# Haptic_Schematic.net
KiCad netlist of a schematic drawn in EAGLE
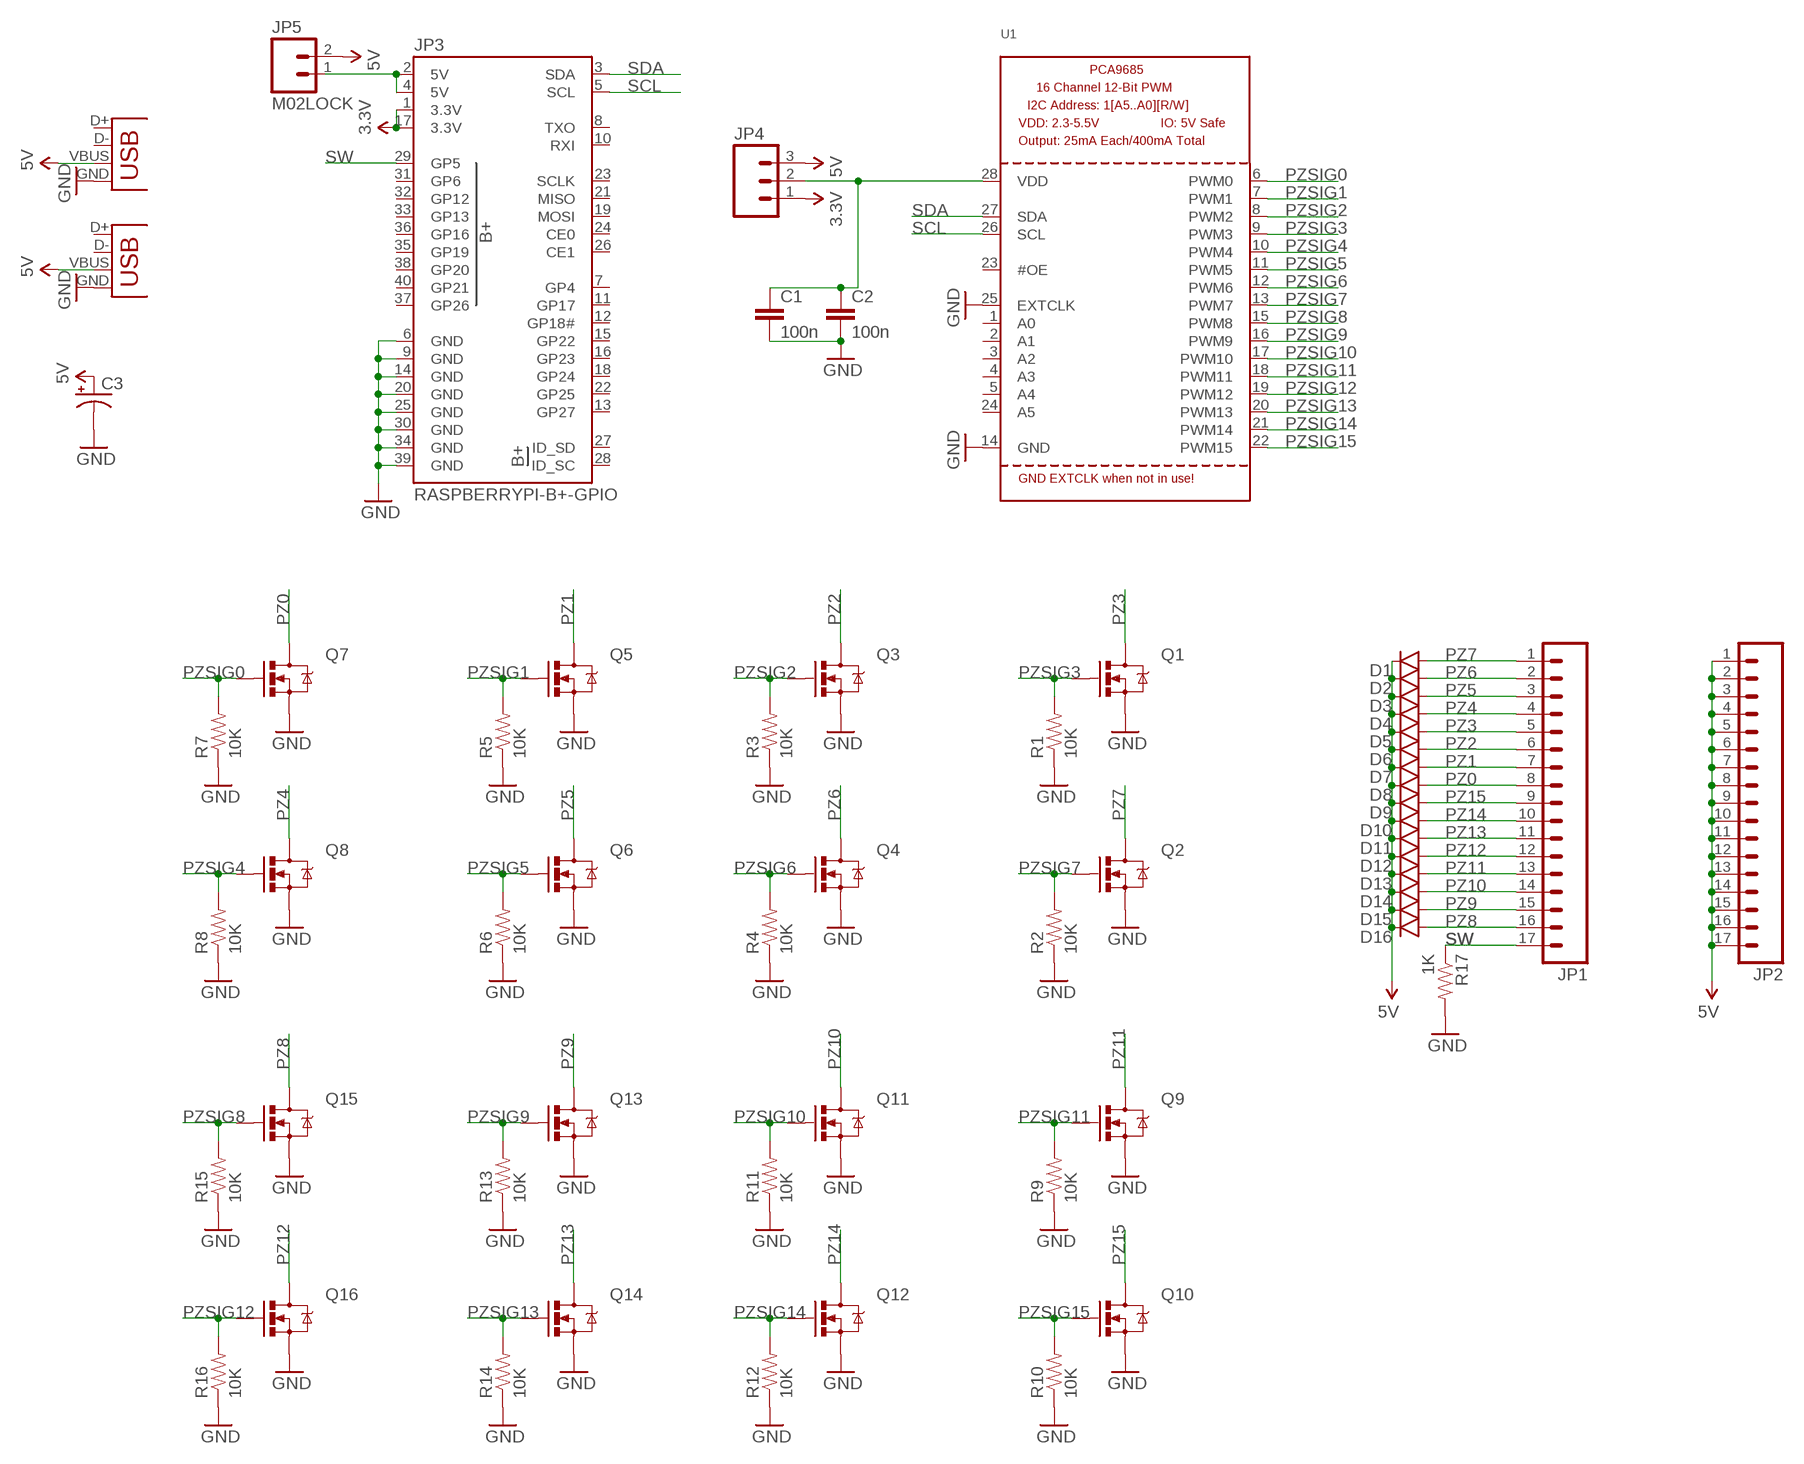
[diagram p0: schematic, sheet 1]

(export (version "E")
  (design (tool "Eeschema 10.0.6"))
  (components
    (comp (ref "C1")
      (value "100n")
      (footprint "eagle-import:0805")
      (libsource (lib "eagle-import") (part "CAP0805"))
    )
    (comp (ref "C2")
      (value "100n")
      (footprint "eagle-import:0805")
      (libsource (lib "eagle-import") (part "CAP0805"))
    )
    (comp (ref "C3")
      (value "CAP_POLPTH2")
      (footprint "eagle-import:CPOL-RADIAL-10UF-25V")
      (libsource (lib "eagle-import") (part "CAP_POLPTH2"))
    )
    (comp (ref "D1")
      (value "DIODESOD523")
      (footprint "eagle-import:SOD523")
      (libsource (lib "eagle-import") (part "DIODESOD523"))
    )
    (comp (ref "D2")
      (value "DIODESOD523")
      (footprint "eagle-import:SOD523")
      (libsource (lib "eagle-import") (part "DIODESOD523"))
    )
    (comp (ref "D3")
      (value "DIODESOD523")
      (footprint "eagle-import:SOD523")
      (libsource (lib "eagle-import") (part "DIODESOD523"))
    )
    (comp (ref "D4")
      (value "DIODESOD523")
      (footprint "eagle-import:SOD523")
      (libsource (lib "eagle-import") (part "DIODESOD523"))
    )
    (comp (ref "D5")
      (value "DIODESOD523")
      (footprint "eagle-import:SOD523")
      (libsource (lib "eagle-import") (part "DIODESOD523"))
    )
    (comp (ref "D6")
      (value "DIODESOD523")
      (footprint "eagle-import:SOD523")
      (libsource (lib "eagle-import") (part "DIODESOD523"))
    )
    (comp (ref "D7")
      (value "DIODESOD523")
      (footprint "eagle-import:SOD523")
      (libsource (lib "eagle-import") (part "DIODESOD523"))
    )
    (comp (ref "D8")
      (value "DIODESOD523")
      (footprint "eagle-import:SOD523")
      (libsource (lib "eagle-import") (part "DIODESOD523"))
    )
    (comp (ref "D9")
      (value "DIODESOD523")
      (footprint "eagle-import:SOD523")
      (libsource (lib "eagle-import") (part "DIODESOD523"))
    )
    (comp (ref "D10")
      (value "DIODESOD523")
      (footprint "eagle-import:SOD523")
      (libsource (lib "eagle-import") (part "DIODESOD523"))
    )
    (comp (ref "D11")
      (value "DIODESOD523")
      (footprint "eagle-import:SOD523")
      (libsource (lib "eagle-import") (part "DIODESOD523"))
    )
    (comp (ref "D12")
      (value "DIODESOD523")
      (footprint "eagle-import:SOD523")
      (libsource (lib "eagle-import") (part "DIODESOD523"))
    )
    (comp (ref "D13")
      (value "DIODESOD523")
      (footprint "eagle-import:SOD523")
      (libsource (lib "eagle-import") (part "DIODESOD523"))
    )
    (comp (ref "D14")
      (value "DIODESOD523")
      (footprint "eagle-import:SOD523")
      (libsource (lib "eagle-import") (part "DIODESOD523"))
    )
    (comp (ref "D15")
      (value "DIODESOD523")
      (footprint "eagle-import:SOD523")
      (libsource (lib "eagle-import") (part "DIODESOD523"))
    )
    (comp (ref "D16")
      (value "DIODESOD523")
      (footprint "eagle-import:SOD523")
      (libsource (lib "eagle-import") (part "DIODESOD523"))
    )
    (comp (ref "JP1")
      (value "M17")
      (footprint "eagle-import:1X17")
      (libsource (lib "eagle-import") (part "M17"))
    )
    (comp (ref "JP2")
      (value "M17")
      (footprint "eagle-import:1X17")
      (libsource (lib "eagle-import") (part "M17"))
    )
    (comp (ref "JP3")
      (value "RASPBERRYPI-B+-GPIO")
      (footprint "eagle-import:2X20-SHROUDED")
      (libsource (lib "eagle-import") (part "RASPBERRYPI-B+-GPIO"))
    )
    (comp (ref "JP4")
      (value "M03LOCK")
      (footprint "eagle-import:1X03_LOCK")
      (libsource (lib "eagle-import") (part "M03LOCK"))
    )
    (comp (ref "JP5")
      (value "M02LOCK")
      (footprint "eagle-import:1X02_LOCK")
      (libsource (lib "eagle-import") (part "M02LOCK"))
    )
    (comp (ref "JP6")
      (value "USB-B")
      (footprint "eagle-import:USB-B-PTH")
      (libsource (lib "eagle-import") (part "USBPTH"))
    )
    (comp (ref "JP7")
      (value "USB-B")
      (footprint "eagle-import:USB-B-PTH")
      (libsource (lib "eagle-import") (part "USBPTH"))
    )
    (comp (ref "Q1")
      (value "MOSFET-NCHANNEL2N7002PW")
      (footprint "eagle-import:SOT323")
      (libsource (lib "eagle-import") (part "MOSFET-NCHANNEL2N7002PW"))
    )
    (comp (ref "Q2")
      (value "MOSFET-NCHANNEL2N7002PW")
      (footprint "eagle-import:SOT323")
      (libsource (lib "eagle-import") (part "MOSFET-NCHANNEL2N7002PW"))
    )
    (comp (ref "Q3")
      (value "MOSFET-NCHANNEL2N7002PW")
      (footprint "eagle-import:SOT323")
      (libsource (lib "eagle-import") (part "MOSFET-NCHANNEL2N7002PW"))
    )
    (comp (ref "Q4")
      (value "MOSFET-NCHANNEL2N7002PW")
      (footprint "eagle-import:SOT323")
      (libsource (lib "eagle-import") (part "MOSFET-NCHANNEL2N7002PW"))
    )
    (comp (ref "Q5")
      (value "MOSFET-NCHANNEL2N7002PW")
      (footprint "eagle-import:SOT323")
      (libsource (lib "eagle-import") (part "MOSFET-NCHANNEL2N7002PW"))
    )
    (comp (ref "Q6")
      (value "MOSFET-NCHANNEL2N7002PW")
      (footprint "eagle-import:SOT323")
      (libsource (lib "eagle-import") (part "MOSFET-NCHANNEL2N7002PW"))
    )
    (comp (ref "Q7")
      (value "MOSFET-NCHANNEL2N7002PW")
      (footprint "eagle-import:SOT323")
      (libsource (lib "eagle-import") (part "MOSFET-NCHANNEL2N7002PW"))
    )
    (comp (ref "Q8")
      (value "MOSFET-NCHANNEL2N7002PW")
      (footprint "eagle-import:SOT323")
      (libsource (lib "eagle-import") (part "MOSFET-NCHANNEL2N7002PW"))
    )
    (comp (ref "Q9")
      (value "MOSFET-NCHANNEL2N7002PW")
      (footprint "eagle-import:SOT323")
      (libsource (lib "eagle-import") (part "MOSFET-NCHANNEL2N7002PW"))
    )
    (comp (ref "Q10")
      (value "MOSFET-NCHANNEL2N7002PW")
      (footprint "eagle-import:SOT323")
      (libsource (lib "eagle-import") (part "MOSFET-NCHANNEL2N7002PW"))
    )
    (comp (ref "Q11")
      (value "MOSFET-NCHANNEL2N7002PW")
      (footprint "eagle-import:SOT323")
      (libsource (lib "eagle-import") (part "MOSFET-NCHANNEL2N7002PW"))
    )
    (comp (ref "Q12")
      (value "MOSFET-NCHANNEL2N7002PW")
      (footprint "eagle-import:SOT323")
      (libsource (lib "eagle-import") (part "MOSFET-NCHANNEL2N7002PW"))
    )
    (comp (ref "Q13")
      (value "MOSFET-NCHANNEL2N7002PW")
      (footprint "eagle-import:SOT323")
      (libsource (lib "eagle-import") (part "MOSFET-NCHANNEL2N7002PW"))
    )
    (comp (ref "Q14")
      (value "MOSFET-NCHANNEL2N7002PW")
      (footprint "eagle-import:SOT323")
      (libsource (lib "eagle-import") (part "MOSFET-NCHANNEL2N7002PW"))
    )
    (comp (ref "Q15")
      (value "MOSFET-NCHANNEL2N7002PW")
      (footprint "eagle-import:SOT323")
      (libsource (lib "eagle-import") (part "MOSFET-NCHANNEL2N7002PW"))
    )
    (comp (ref "Q16")
      (value "MOSFET-NCHANNEL2N7002PW")
      (footprint "eagle-import:SOT323")
      (libsource (lib "eagle-import") (part "MOSFET-NCHANNEL2N7002PW"))
    )
    (comp (ref "R1")
      (value "10K")
      (footprint "eagle-import:0805")
      (libsource (lib "eagle-import") (part "RESISTOR0805-RES"))
    )
    (comp (ref "R2")
      (value "10K")
      (footprint "eagle-import:0805")
      (libsource (lib "eagle-import") (part "RESISTOR0805-RES"))
    )
    (comp (ref "R3")
      (value "10K")
      (footprint "eagle-import:0805")
      (libsource (lib "eagle-import") (part "RESISTOR0805-RES"))
    )
    (comp (ref "R4")
      (value "10K")
      (footprint "eagle-import:0805")
      (libsource (lib "eagle-import") (part "RESISTOR0805-RES"))
    )
    (comp (ref "R5")
      (value "10K")
      (footprint "eagle-import:0805")
      (libsource (lib "eagle-import") (part "RESISTOR0805-RES"))
    )
    (comp (ref "R6")
      (value "10K")
      (footprint "eagle-import:0805")
      (libsource (lib "eagle-import") (part "RESISTOR0805-RES"))
    )
    (comp (ref "R7")
      (value "10K")
      (footprint "eagle-import:0805")
      (libsource (lib "eagle-import") (part "RESISTOR0805-RES"))
    )
    (comp (ref "R8")
      (value "10K")
      (footprint "eagle-import:0805")
      (libsource (lib "eagle-import") (part "RESISTOR0805-RES"))
    )
    (comp (ref "R9")
      (value "10K")
      (footprint "eagle-import:0805")
      (libsource (lib "eagle-import") (part "RESISTOR0805-RES"))
    )
    (comp (ref "R10")
      (value "10K")
      (footprint "eagle-import:0805")
      (libsource (lib "eagle-import") (part "RESISTOR0805-RES"))
    )
    (comp (ref "R11")
      (value "10K")
      (footprint "eagle-import:0805")
      (libsource (lib "eagle-import") (part "RESISTOR0805-RES"))
    )
    (comp (ref "R12")
      (value "10K")
      (footprint "eagle-import:0805")
      (libsource (lib "eagle-import") (part "RESISTOR0805-RES"))
    )
    (comp (ref "R13")
      (value "10K")
      (footprint "eagle-import:0805")
      (libsource (lib "eagle-import") (part "RESISTOR0805-RES"))
    )
    (comp (ref "R14")
      (value "10K")
      (footprint "eagle-import:0805")
      (libsource (lib "eagle-import") (part "RESISTOR0805-RES"))
    )
    (comp (ref "R15")
      (value "10K")
      (footprint "eagle-import:0805")
      (libsource (lib "eagle-import") (part "RESISTOR0805-RES"))
    )
    (comp (ref "R16")
      (value "10K")
      (footprint "eagle-import:0805")
      (libsource (lib "eagle-import") (part "RESISTOR0805-RES"))
    )
    (comp (ref "R17")
      (value "1K")
      (footprint "eagle-import:0805")
      (libsource (lib "eagle-import") (part "RESISTOR0805-RES"))
    )
    (comp (ref "U1")
      (value "PCA9685")
      (footprint "eagle-import:TSSOP28")
      (libsource (lib "eagle-import") (part "PCA9685"))
    )
  )
  (nets
    (net (code "1") (name "/PZ0") (class "Default")
      (node (ref "D8") (pin "A") (pinfunction "A_A") (pintype "passive"))
      (node (ref "JP1") (pin "8") (pinfunction "8_8") (pintype "passive"))
      (node (ref "Q7") (pin "3") (pinfunction "D_3") (pintype "passive"))
    )
    (net (code "2") (name "/PZ1") (class "Default")
      (node (ref "D7") (pin "A") (pinfunction "A_A") (pintype "passive"))
      (node (ref "JP1") (pin "7") (pinfunction "7_7") (pintype "passive"))
      (node (ref "Q5") (pin "3") (pinfunction "D_3") (pintype "passive"))
    )
    (net (code "3") (name "/PZ2") (class "Default")
      (node (ref "D6") (pin "A") (pinfunction "A_A") (pintype "passive"))
      (node (ref "JP1") (pin "6") (pinfunction "6_6") (pintype "passive"))
      (node (ref "Q3") (pin "3") (pinfunction "D_3") (pintype "passive"))
    )
    (net (code "4") (name "/PZ3") (class "Default")
      (node (ref "D5") (pin "A") (pinfunction "A_A") (pintype "passive"))
      (node (ref "JP1") (pin "5") (pinfunction "5_5") (pintype "passive"))
      (node (ref "Q1") (pin "3") (pinfunction "D_3") (pintype "passive"))
    )
    (net (code "5") (name "/PZ4") (class "Default")
      (node (ref "D4") (pin "A") (pinfunction "A_A") (pintype "passive"))
      (node (ref "JP1") (pin "4") (pinfunction "4_4") (pintype "passive"))
      (node (ref "Q8") (pin "3") (pinfunction "D_3") (pintype "passive"))
    )
    (net (code "6") (name "/PZ5") (class "Default")
      (node (ref "D3") (pin "A") (pinfunction "A_A") (pintype "passive"))
      (node (ref "JP1") (pin "3") (pinfunction "3_3") (pintype "passive"))
      (node (ref "Q6") (pin "3") (pinfunction "D_3") (pintype "passive"))
    )
    (net (code "7") (name "/PZ6") (class "Default")
      (node (ref "D2") (pin "A") (pinfunction "A_A") (pintype "passive"))
      (node (ref "JP1") (pin "2") (pinfunction "2_2") (pintype "passive"))
      (node (ref "Q4") (pin "3") (pinfunction "D_3") (pintype "passive"))
    )
    (net (code "8") (name "/PZ7") (class "Default")
      (node (ref "D1") (pin "A") (pinfunction "A_A") (pintype "passive"))
      (node (ref "JP1") (pin "1") (pinfunction "1_1") (pintype "passive"))
      (node (ref "Q2") (pin "3") (pinfunction "D_3") (pintype "passive"))
    )
    (net (code "9") (name "/PZ8") (class "Default")
      (node (ref "D16") (pin "A") (pinfunction "A_A") (pintype "passive"))
      (node (ref "JP1") (pin "16") (pinfunction "16_16") (pintype "passive"))
      (node (ref "Q15") (pin "3") (pinfunction "D_3") (pintype "passive"))
    )
    (net (code "10") (name "/PZ9") (class "Default")
      (node (ref "D15") (pin "A") (pinfunction "A_A") (pintype "passive"))
      (node (ref "JP1") (pin "15") (pinfunction "15_15") (pintype "passive"))
      (node (ref "Q13") (pin "3") (pinfunction "D_3") (pintype "passive"))
    )
    (net (code "11") (name "/PZ10") (class "Default")
      (node (ref "D14") (pin "A") (pinfunction "A_A") (pintype "passive"))
      (node (ref "JP1") (pin "14") (pinfunction "14_14") (pintype "passive"))
      (node (ref "Q11") (pin "3") (pinfunction "D_3") (pintype "passive"))
    )
    (net (code "12") (name "/PZ11") (class "Default")
      (node (ref "D13") (pin "A") (pinfunction "A_A") (pintype "passive"))
      (node (ref "JP1") (pin "13") (pinfunction "13_13") (pintype "passive"))
      (node (ref "Q9") (pin "3") (pinfunction "D_3") (pintype "passive"))
    )
    (net (code "13") (name "/PZ12") (class "Default")
      (node (ref "D12") (pin "A") (pinfunction "A_A") (pintype "passive"))
      (node (ref "JP1") (pin "12") (pinfunction "12_12") (pintype "passive"))
      (node (ref "Q16") (pin "3") (pinfunction "D_3") (pintype "passive"))
    )
    (net (code "14") (name "/PZ13") (class "Default")
      (node (ref "D11") (pin "A") (pinfunction "A_A") (pintype "passive"))
      (node (ref "JP1") (pin "11") (pinfunction "11_11") (pintype "passive"))
      (node (ref "Q14") (pin "3") (pinfunction "D_3") (pintype "passive"))
    )
    (net (code "15") (name "/PZ14") (class "Default")
      (node (ref "D10") (pin "A") (pinfunction "A_A") (pintype "passive"))
      (node (ref "JP1") (pin "10") (pinfunction "10_10") (pintype "passive"))
      (node (ref "Q12") (pin "3") (pinfunction "D_3") (pintype "passive"))
    )
    (net (code "16") (name "/PZ15") (class "Default")
      (node (ref "D9") (pin "A") (pinfunction "A_A") (pintype "passive"))
      (node (ref "JP1") (pin "9") (pinfunction "9_9") (pintype "passive"))
      (node (ref "Q10") (pin "3") (pinfunction "D_3") (pintype "passive"))
    )
    (net (code "17") (name "/PZSIG0") (class "Default")
      (node (ref "Q7") (pin "1") (pinfunction "G_1") (pintype "passive"))
      (node (ref "R7") (pin "2") (pinfunction "2_2") (pintype "passive"))
      (node (ref "U1") (pin "6") (pinfunction "PWM0_6") (pintype "output"))
    )
    (net (code "18") (name "/PZSIG1") (class "Default")
      (node (ref "Q5") (pin "1") (pinfunction "G_1") (pintype "passive"))
      (node (ref "R5") (pin "2") (pinfunction "2_2") (pintype "passive"))
      (node (ref "U1") (pin "7") (pinfunction "PWM1_7") (pintype "output"))
    )
    (net (code "19") (name "/PZSIG2") (class "Default")
      (node (ref "Q3") (pin "1") (pinfunction "G_1") (pintype "passive"))
      (node (ref "R3") (pin "2") (pinfunction "2_2") (pintype "passive"))
      (node (ref "U1") (pin "8") (pinfunction "PWM2_8") (pintype "output"))
    )
    (net (code "20") (name "/PZSIG3") (class "Default")
      (node (ref "Q1") (pin "1") (pinfunction "G_1") (pintype "passive"))
      (node (ref "R1") (pin "2") (pinfunction "2_2") (pintype "passive"))
      (node (ref "U1") (pin "9") (pinfunction "PWM3_9") (pintype "output"))
    )
    (net (code "21") (name "/PZSIG4") (class "Default")
      (node (ref "Q8") (pin "1") (pinfunction "G_1") (pintype "passive"))
      (node (ref "R8") (pin "2") (pinfunction "2_2") (pintype "passive"))
      (node (ref "U1") (pin "10") (pinfunction "PWM4_10") (pintype "output"))
    )
    (net (code "22") (name "/PZSIG5") (class "Default")
      (node (ref "Q6") (pin "1") (pinfunction "G_1") (pintype "passive"))
      (node (ref "R6") (pin "2") (pinfunction "2_2") (pintype "passive"))
      (node (ref "U1") (pin "11") (pinfunction "PWM5_11") (pintype "output"))
    )
    (net (code "23") (name "/PZSIG6") (class "Default")
      (node (ref "Q4") (pin "1") (pinfunction "G_1") (pintype "passive"))
      (node (ref "R4") (pin "2") (pinfunction "2_2") (pintype "passive"))
      (node (ref "U1") (pin "12") (pinfunction "PWM6_12") (pintype "output"))
    )
    (net (code "24") (name "/PZSIG7") (class "Default")
      (node (ref "Q2") (pin "1") (pinfunction "G_1") (pintype "passive"))
      (node (ref "R2") (pin "2") (pinfunction "2_2") (pintype "passive"))
      (node (ref "U1") (pin "13") (pinfunction "PWM7_13") (pintype "output"))
    )
    (net (code "25") (name "/PZSIG8") (class "Default")
      (node (ref "Q15") (pin "1") (pinfunction "G_1") (pintype "passive"))
      (node (ref "R15") (pin "2") (pinfunction "2_2") (pintype "passive"))
      (node (ref "U1") (pin "15") (pinfunction "PWM8_15") (pintype "output"))
    )
    (net (code "26") (name "/PZSIG9") (class "Default")
      (node (ref "Q13") (pin "1") (pinfunction "G_1") (pintype "passive"))
      (node (ref "R13") (pin "2") (pinfunction "2_2") (pintype "passive"))
      (node (ref "U1") (pin "16") (pinfunction "PWM9_16") (pintype "output"))
    )
    (net (code "27") (name "/PZSIG10") (class "Default")
      (node (ref "Q11") (pin "1") (pinfunction "G_1") (pintype "passive"))
      (node (ref "R11") (pin "2") (pinfunction "2_2") (pintype "passive"))
      (node (ref "U1") (pin "17") (pinfunction "PWM10_17") (pintype "output"))
    )
    (net (code "28") (name "/PZSIG11") (class "Default")
      (node (ref "Q9") (pin "1") (pinfunction "G_1") (pintype "passive"))
      (node (ref "R9") (pin "2") (pinfunction "2_2") (pintype "passive"))
      (node (ref "U1") (pin "18") (pinfunction "PWM11_18") (pintype "output"))
    )
    (net (code "29") (name "/PZSIG12") (class "Default")
      (node (ref "Q16") (pin "1") (pinfunction "G_1") (pintype "passive"))
      (node (ref "R16") (pin "2") (pinfunction "2_2") (pintype "passive"))
      (node (ref "U1") (pin "19") (pinfunction "PWM12_19") (pintype "output"))
    )
    (net (code "30") (name "/PZSIG13") (class "Default")
      (node (ref "Q14") (pin "1") (pinfunction "G_1") (pintype "passive"))
      (node (ref "R14") (pin "2") (pinfunction "2_2") (pintype "passive"))
      (node (ref "U1") (pin "20") (pinfunction "PWM13_20") (pintype "output"))
    )
    (net (code "31") (name "/PZSIG14") (class "Default")
      (node (ref "Q12") (pin "1") (pinfunction "G_1") (pintype "passive"))
      (node (ref "R12") (pin "2") (pinfunction "2_2") (pintype "passive"))
      (node (ref "U1") (pin "21") (pinfunction "PWM14_21") (pintype "output"))
    )
    (net (code "32") (name "/PZSIG15") (class "Default")
      (node (ref "Q10") (pin "1") (pinfunction "G_1") (pintype "passive"))
      (node (ref "R10") (pin "2") (pinfunction "2_2") (pintype "passive"))
      (node (ref "U1") (pin "22") (pinfunction "PWM15_22") (pintype "output"))
    )
    (net (code "33") (name "/SCL") (class "Default")
      (node (ref "JP3") (pin "5") (pinfunction "SCL_5") (pintype "bidirectional"))
      (node (ref "U1") (pin "26") (pinfunction "SCL_26") (pintype "bidirectional"))
    )
    (net (code "34") (name "/SDA") (class "Default")
      (node (ref "JP3") (pin "3") (pinfunction "SDA_3") (pintype "bidirectional"))
      (node (ref "U1") (pin "27") (pinfunction "SDA_27") (pintype "bidirectional"))
    )
    (net (code "35") (name "/SW") (class "Default")
      (node (ref "JP1") (pin "17") (pinfunction "17_17") (pintype "passive"))
      (node (ref "JP3") (pin "29") (pinfunction "GP5_29") (pintype "bidirectional"))
      (node (ref "R17") (pin "1") (pinfunction "1_1") (pintype "passive"))
    )
    (net (code "36") (name "3.3V") (class "Default")
      (node (ref "JP3") (pin "1") (pinfunction "3.3V_1") (pintype "power_in"))
      (node (ref "JP3") (pin "17") (pinfunction "3.3V_17") (pintype "power_in"))
      (node (ref "JP4") (pin "1") (pinfunction "1_1") (pintype "passive"))
    )
    (net (code "37") (name "5V") (class "Default")
      (node (ref "C3") (pin "1") (pinfunction "+_1") (pintype "passive"))
      (node (ref "D1") (pin "C") (pinfunction "C_C") (pintype "passive"))
      (node (ref "D10") (pin "C") (pinfunction "C_C") (pintype "passive"))
      (node (ref "D11") (pin "C") (pinfunction "C_C") (pintype "passive"))
      (node (ref "D12") (pin "C") (pinfunction "C_C") (pintype "passive"))
      (node (ref "D13") (pin "C") (pinfunction "C_C") (pintype "passive"))
      (node (ref "D14") (pin "C") (pinfunction "C_C") (pintype "passive"))
      (node (ref "D15") (pin "C") (pinfunction "C_C") (pintype "passive"))
      (node (ref "D16") (pin "C") (pinfunction "C_C") (pintype "passive"))
      (node (ref "D2") (pin "C") (pinfunction "C_C") (pintype "passive"))
      (node (ref "D3") (pin "C") (pinfunction "C_C") (pintype "passive"))
      (node (ref "D4") (pin "C") (pinfunction "C_C") (pintype "passive"))
      (node (ref "D5") (pin "C") (pinfunction "C_C") (pintype "passive"))
      (node (ref "D6") (pin "C") (pinfunction "C_C") (pintype "passive"))
      (node (ref "D7") (pin "C") (pinfunction "C_C") (pintype "passive"))
      (node (ref "D8") (pin "C") (pinfunction "C_C") (pintype "passive"))
      (node (ref "D9") (pin "C") (pinfunction "C_C") (pintype "passive"))
      (node (ref "JP2") (pin "1") (pinfunction "1_1") (pintype "passive"))
      (node (ref "JP2") (pin "10") (pinfunction "10_10") (pintype "passive"))
      (node (ref "JP2") (pin "11") (pinfunction "11_11") (pintype "passive"))
      (node (ref "JP2") (pin "12") (pinfunction "12_12") (pintype "passive"))
      (node (ref "JP2") (pin "13") (pinfunction "13_13") (pintype "passive"))
      (node (ref "JP2") (pin "14") (pinfunction "14_14") (pintype "passive"))
      (node (ref "JP2") (pin "15") (pinfunction "15_15") (pintype "passive"))
      (node (ref "JP2") (pin "16") (pinfunction "16_16") (pintype "passive"))
      (node (ref "JP2") (pin "17") (pinfunction "17_17") (pintype "passive"))
      (node (ref "JP2") (pin "2") (pinfunction "2_2") (pintype "passive"))
      (node (ref "JP2") (pin "3") (pinfunction "3_3") (pintype "passive"))
      (node (ref "JP2") (pin "4") (pinfunction "4_4") (pintype "passive"))
      (node (ref "JP2") (pin "5") (pinfunction "5_5") (pintype "passive"))
      (node (ref "JP2") (pin "6") (pinfunction "6_6") (pintype "passive"))
      (node (ref "JP2") (pin "7") (pinfunction "7_7") (pintype "passive"))
      (node (ref "JP2") (pin "8") (pinfunction "8_8") (pintype "passive"))
      (node (ref "JP2") (pin "9") (pinfunction "9_9") (pintype "passive"))
      (node (ref "JP4") (pin "3") (pinfunction "3_3") (pintype "passive"))
      (node (ref "JP5") (pin "2") (pinfunction "2_2") (pintype "passive"))
      (node (ref "JP6") (pin "VBUS") (pinfunction "VBUS_VBUS") (pintype "bidirectional"))
      (node (ref "JP7") (pin "VBUS") (pinfunction "VBUS_VBUS") (pintype "bidirectional"))
    )
    (net (code "38") (name "GND") (class "Default")
      (node (ref "C1") (pin "2") (pinfunction "2_2") (pintype "passive"))
      (node (ref "C2") (pin "2") (pinfunction "2_2") (pintype "passive"))
      (node (ref "C3") (pin "2") (pinfunction "-_2") (pintype "passive"))
      (node (ref "JP3") (pin "14") (pinfunction "GND_14") (pintype "power_in"))
      (node (ref "JP3") (pin "20") (pinfunction "GND_20") (pintype "power_in"))
      (node (ref "JP3") (pin "25") (pinfunction "GND_25") (pintype "power_in"))
      (node (ref "JP3") (pin "30") (pinfunction "GND_30") (pintype "power_in"))
      (node (ref "JP3") (pin "34") (pinfunction "GND_34") (pintype "power_in"))
      (node (ref "JP3") (pin "39") (pinfunction "GND_39") (pintype "power_in"))
      (node (ref "JP3") (pin "6") (pinfunction "GND_6") (pintype "power_in"))
      (node (ref "JP3") (pin "9") (pinfunction "GND_9") (pintype "power_in"))
      (node (ref "JP6") (pin "GND") (pinfunction "GND_GND") (pintype "bidirectional"))
      (node (ref "JP7") (pin "GND") (pinfunction "GND_GND") (pintype "bidirectional"))
      (node (ref "Q1") (pin "2") (pinfunction "S_2") (pintype "passive"))
      (node (ref "Q10") (pin "2") (pinfunction "S_2") (pintype "passive"))
      (node (ref "Q11") (pin "2") (pinfunction "S_2") (pintype "passive"))
      (node (ref "Q12") (pin "2") (pinfunction "S_2") (pintype "passive"))
      (node (ref "Q13") (pin "2") (pinfunction "S_2") (pintype "passive"))
      (node (ref "Q14") (pin "2") (pinfunction "S_2") (pintype "passive"))
      (node (ref "Q15") (pin "2") (pinfunction "S_2") (pintype "passive"))
      (node (ref "Q16") (pin "2") (pinfunction "S_2") (pintype "passive"))
      (node (ref "Q2") (pin "2") (pinfunction "S_2") (pintype "passive"))
      (node (ref "Q3") (pin "2") (pinfunction "S_2") (pintype "passive"))
      (node (ref "Q4") (pin "2") (pinfunction "S_2") (pintype "passive"))
      (node (ref "Q5") (pin "2") (pinfunction "S_2") (pintype "passive"))
      (node (ref "Q6") (pin "2") (pinfunction "S_2") (pintype "passive"))
      (node (ref "Q7") (pin "2") (pinfunction "S_2") (pintype "passive"))
      (node (ref "Q8") (pin "2") (pinfunction "S_2") (pintype "passive"))
      (node (ref "Q9") (pin "2") (pinfunction "S_2") (pintype "passive"))
      (node (ref "R1") (pin "1") (pinfunction "1_1") (pintype "passive"))
      (node (ref "R10") (pin "1") (pinfunction "1_1") (pintype "passive"))
      (node (ref "R11") (pin "1") (pinfunction "1_1") (pintype "passive"))
      (node (ref "R12") (pin "1") (pinfunction "1_1") (pintype "passive"))
      (node (ref "R13") (pin "1") (pinfunction "1_1") (pintype "passive"))
      (node (ref "R14") (pin "1") (pinfunction "1_1") (pintype "passive"))
      (node (ref "R15") (pin "1") (pinfunction "1_1") (pintype "passive"))
      (node (ref "R16") (pin "1") (pinfunction "1_1") (pintype "passive"))
      (node (ref "R17") (pin "2") (pinfunction "2_2") (pintype "passive"))
      (node (ref "R2") (pin "1") (pinfunction "1_1") (pintype "passive"))
      (node (ref "R3") (pin "1") (pinfunction "1_1") (pintype "passive"))
      (node (ref "R4") (pin "1") (pinfunction "1_1") (pintype "passive"))
      (node (ref "R5") (pin "1") (pinfunction "1_1") (pintype "passive"))
      (node (ref "R6") (pin "1") (pinfunction "1_1") (pintype "passive"))
      (node (ref "R7") (pin "1") (pinfunction "1_1") (pintype "passive"))
      (node (ref "R8") (pin "1") (pinfunction "1_1") (pintype "passive"))
      (node (ref "R9") (pin "1") (pinfunction "1_1") (pintype "passive"))
      (node (ref "U1") (pin "14") (pinfunction "GND_14") (pintype "power_in"))
      (node (ref "U1") (pin "25") (pinfunction "EXTCLK_25") (pintype "input"))
    )
    (net (code "39") (name "Net-(JP3-5V-Pad2)") (class "Default")
      (node (ref "JP3") (pin "2") (pinfunction "5V_2") (pintype "power_in"))
      (node (ref "JP3") (pin "4") (pinfunction "5V_4") (pintype "power_in"))
      (node (ref "JP5") (pin "1") (pinfunction "1_1") (pintype "passive"))
    )
    (net (code "40") (name "Net-(U1-VDD)") (class "Default")
      (node (ref "C1") (pin "1") (pinfunction "1_1") (pintype "passive"))
      (node (ref "C2") (pin "1") (pinfunction "1_1") (pintype "passive"))
      (node (ref "JP4") (pin "2") (pinfunction "2_2") (pintype "passive"))
      (node (ref "U1") (pin "28") (pinfunction "VDD_28") (pintype "power_in"))
    )
    (net (code "41") (name "unconnected-(JP3-CE0-Pad24)") (class "Default")
      (node (ref "JP3") (pin "24") (pinfunction "CE0_24") (pintype "output"))
    )
    (net (code "42") (name "unconnected-(JP3-CE1-Pad26)") (class "Default")
      (node (ref "JP3") (pin "26") (pinfunction "CE1_26") (pintype "output"))
    )
    (net (code "43") (name "unconnected-(JP3-GP4-Pad7)") (class "Default")
      (node (ref "JP3") (pin "7") (pinfunction "GP4_7") (pintype "bidirectional"))
    )
    (net (code "44") (name "unconnected-(JP3-GP6-Pad31)") (class "Default")
      (node (ref "JP3") (pin "31") (pinfunction "GP6_31") (pintype "bidirectional"))
    )
    (net (code "45") (name "unconnected-(JP3-GP12-Pad32)") (class "Default")
      (node (ref "JP3") (pin "32") (pinfunction "GP12_32") (pintype "bidirectional"))
    )
    (net (code "46") (name "unconnected-(JP3-GP13-Pad33)") (class "Default")
      (node (ref "JP3") (pin "33") (pinfunction "GP13_33") (pintype "bidirectional"))
    )
    (net (code "47") (name "unconnected-(JP3-GP16-Pad36)") (class "Default")
      (node (ref "JP3") (pin "36") (pinfunction "GP16_36") (pintype "bidirectional"))
    )
    (net (code "48") (name "unconnected-(JP3-GP17-Pad11)") (class "Default")
      (node (ref "JP3") (pin "11") (pinfunction "GP17_11") (pintype "bidirectional"))
    )
    (net (code "49") (name "unconnected-(JP3-GP18#-Pad12)") (class "Default")
      (node (ref "JP3") (pin "12") (pinfunction "GP18#_12") (pintype "bidirectional"))
    )
    (net (code "50") (name "unconnected-(JP3-GP19-Pad35)") (class "Default")
      (node (ref "JP3") (pin "35") (pinfunction "GP19_35") (pintype "bidirectional"))
    )
    (net (code "51") (name "unconnected-(JP3-GP20-Pad38)") (class "Default")
      (node (ref "JP3") (pin "38") (pinfunction "GP20_38") (pintype "bidirectional"))
    )
    (net (code "52") (name "unconnected-(JP3-GP21-Pad40)") (class "Default")
      (node (ref "JP3") (pin "40") (pinfunction "GP21_40") (pintype "bidirectional"))
    )
    (net (code "53") (name "unconnected-(JP3-GP22-Pad15)") (class "Default")
      (node (ref "JP3") (pin "15") (pinfunction "GP22_15") (pintype "bidirectional"))
    )
    (net (code "54") (name "unconnected-(JP3-GP23-Pad16)") (class "Default")
      (node (ref "JP3") (pin "16") (pinfunction "GP23_16") (pintype "bidirectional"))
    )
    (net (code "55") (name "unconnected-(JP3-GP24-Pad18)") (class "Default")
      (node (ref "JP3") (pin "18") (pinfunction "GP24_18") (pintype "bidirectional"))
    )
    (net (code "56") (name "unconnected-(JP3-GP25-Pad22)") (class "Default")
      (node (ref "JP3") (pin "22") (pinfunction "GP25_22") (pintype "bidirectional"))
    )
    (net (code "57") (name "unconnected-(JP3-GP26-Pad37)") (class "Default")
      (node (ref "JP3") (pin "37") (pinfunction "GP26_37") (pintype "bidirectional"))
    )
    (net (code "58") (name "unconnected-(JP3-GP27-Pad13)") (class "Default")
      (node (ref "JP3") (pin "13") (pinfunction "GP27_13") (pintype "bidirectional"))
    )
    (net (code "59") (name "unconnected-(JP3-ID_SC-Pad28)") (class "Default")
      (node (ref "JP3") (pin "28") (pinfunction "ID_SC_28") (pintype "bidirectional"))
    )
    (net (code "60") (name "unconnected-(JP3-ID_SD-Pad27)") (class "Default")
      (node (ref "JP3") (pin "27") (pinfunction "ID_SD_27") (pintype "bidirectional"))
    )
    (net (code "61") (name "unconnected-(JP3-MISO-Pad21)") (class "Default")
      (node (ref "JP3") (pin "21") (pinfunction "MISO_21") (pintype "input"))
    )
    (net (code "62") (name "unconnected-(JP3-MOSI-Pad19)") (class "Default")
      (node (ref "JP3") (pin "19") (pinfunction "MOSI_19") (pintype "output"))
    )
    (net (code "63") (name "unconnected-(JP3-RXI-Pad10)") (class "Default")
      (node (ref "JP3") (pin "10") (pinfunction "RXI_10") (pintype "input"))
    )
    (net (code "64") (name "unconnected-(JP3-SCLK-Pad23)") (class "Default")
      (node (ref "JP3") (pin "23") (pinfunction "SCLK_23") (pintype "output"))
    )
    (net (code "65") (name "unconnected-(JP3-TXO-Pad8)") (class "Default")
      (node (ref "JP3") (pin "8") (pinfunction "TXO_8") (pintype "output"))
    )
    (net (code "66") (name "unconnected-(JP6-PadD+)") (class "Default")
      (node (ref "JP6") (pin "D+") (pinfunction "D+_D+") (pintype "bidirectional"))
    )
    (net (code "67") (name "unconnected-(JP6-PadD-)") (class "Default")
      (node (ref "JP6") (pin "D-") (pinfunction "D-_D-") (pintype "bidirectional"))
    )
    (net (code "68") (name "unconnected-(JP7-PadD+)") (class "Default")
      (node (ref "JP7") (pin "D+") (pinfunction "D+_D+") (pintype "bidirectional"))
    )
    (net (code "69") (name "unconnected-(JP7-PadD-)") (class "Default")
      (node (ref "JP7") (pin "D-") (pinfunction "D-_D-") (pintype "bidirectional"))
    )
    (net (code "70") (name "unconnected-(U1-#OE-Pad23)") (class "Default")
      (node (ref "U1") (pin "23") (pinfunction "#OE_23") (pintype "input"))
    )
    (net (code "71") (name "unconnected-(U1-A0-Pad1)") (class "Default")
      (node (ref "U1") (pin "1") (pinfunction "A0_1") (pintype "bidirectional"))
    )
    (net (code "72") (name "unconnected-(U1-A1-Pad2)") (class "Default")
      (node (ref "U1") (pin "2") (pinfunction "A1_2") (pintype "bidirectional"))
    )
    (net (code "73") (name "unconnected-(U1-A2-Pad3)") (class "Default")
      (node (ref "U1") (pin "3") (pinfunction "A2_3") (pintype "bidirectional"))
    )
    (net (code "74") (name "unconnected-(U1-A3-Pad4)") (class "Default")
      (node (ref "U1") (pin "4") (pinfunction "A3_4") (pintype "bidirectional"))
    )
    (net (code "75") (name "unconnected-(U1-A4-Pad5)") (class "Default")
      (node (ref "U1") (pin "5") (pinfunction "A4_5") (pintype "bidirectional"))
    )
    (net (code "76") (name "unconnected-(U1-A5-Pad24)") (class "Default")
      (node (ref "U1") (pin "24") (pinfunction "A5_24") (pintype "bidirectional"))
    )
  )
)
